# laser_driver.net
KiCad netlist of a schematic drawn in EAGLE
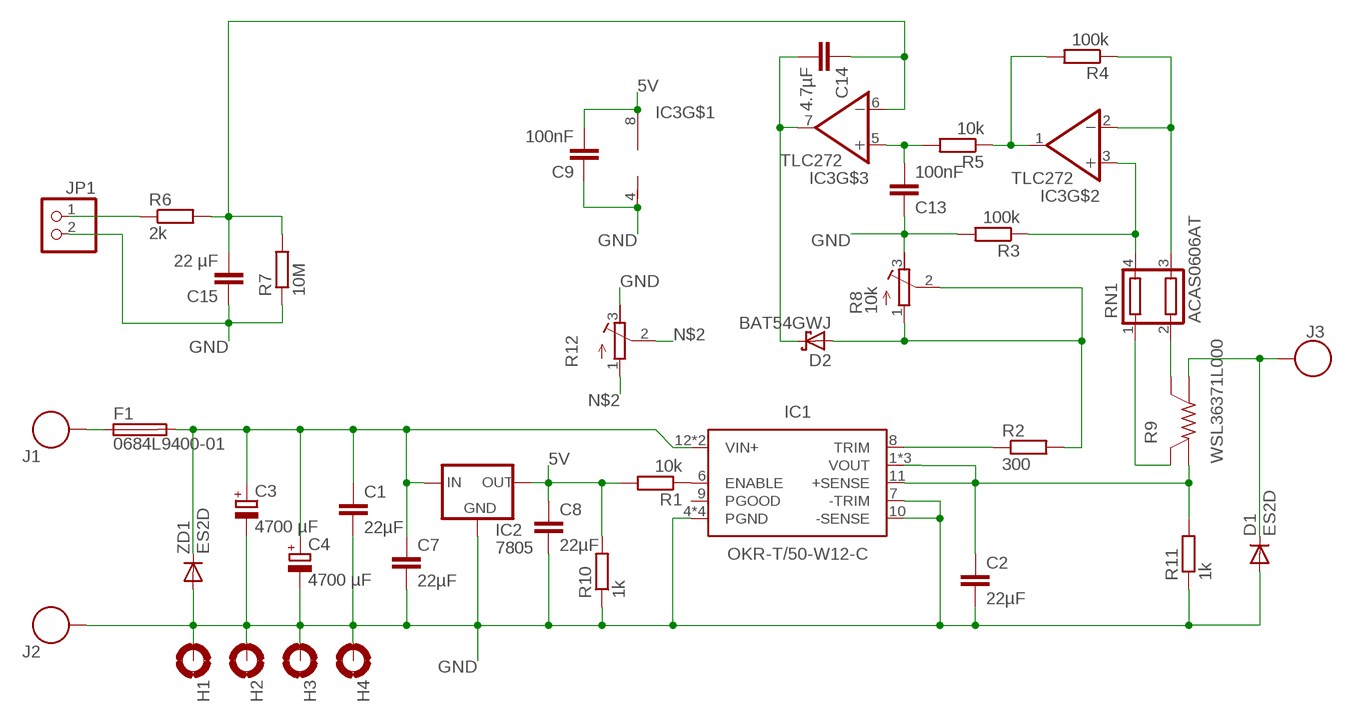
[diagram p0: schematic, sheet 1]

(export (version "E")
  (design (tool "Eeschema 10.0.6"))
  (components
    (comp (ref "C1")
      (value "22µF")
      (footprint "eagle-import:C0805")
      (libsource (lib "eagle-import") (part "C-EUC0805"))
    )
    (comp (ref "C2")
      (value "22µF")
      (footprint "eagle-import:C0805")
      (libsource (lib "eagle-import") (part "C-EUC0805"))
    )
    (comp (ref "C3")
      (value "4700 µF")
      (footprint "eagle-import:E7,5-16")
      (libsource (lib "eagle-import") (part "CPOL-EUE7.5-16"))
    )
    (comp (ref "C4")
      (value "4700 µF")
      (footprint "eagle-import:E7,5-16")
      (libsource (lib "eagle-import") (part "CPOL-EUE7.5-16"))
    )
    (comp (ref "C7")
      (value "22µF")
      (footprint "eagle-import:C0805")
      (libsource (lib "eagle-import") (part "C-EUC0805"))
    )
    (comp (ref "C8")
      (value "22µF")
      (footprint "eagle-import:C0805")
      (libsource (lib "eagle-import") (part "C-EUC0805"))
    )
    (comp (ref "C9")
      (value "100nF")
      (footprint "eagle-import:C0805")
      (libsource (lib "eagle-import") (part "C-EUC0805"))
    )
    (comp (ref "C13")
      (value "100nF")
      (footprint "eagle-import:C0805")
      (libsource (lib "eagle-import") (part "C-EUC0805"))
    )
    (comp (ref "C14")
      (value "4.7µF")
      (footprint "eagle-import:C0805")
      (libsource (lib "eagle-import") (part "C-EUC0805"))
    )
    (comp (ref "C15")
      (value "22 µF")
      (footprint "eagle-import:C0805")
      (libsource (lib "eagle-import") (part "C-EUC0805"))
    )
    (comp (ref "D1")
      (value "ES2D")
      (footprint "eagle-import:SMB")
      (libsource (lib "eagle-import") (part "ES2D"))
    )
    (comp (ref "D2")
      (value "BAT54GWJ")
      (footprint "eagle-import:SOD-123_MINI-SMA")
      (libsource (lib "eagle-import") (part "BAT54GWJ"))
    )
    (comp (ref "F1")
      (value "0684L9400-01")
      (footprint "eagle-import:4818")
      (libsource (lib "eagle-import") (part "0684L9400-01"))
    )
    (comp (ref "H1")
      (value "MOUNT-PAD-ROUND3.0")
      (footprint "eagle-import:3,0-PAD")
      (libsource (lib "eagle-import") (part "MOUNT-PAD-ROUND3.0"))
    )
    (comp (ref "H2")
      (value "MOUNT-PAD-ROUND3.0")
      (footprint "eagle-import:3,0-PAD")
      (libsource (lib "eagle-import") (part "MOUNT-PAD-ROUND3.0"))
    )
    (comp (ref "H3")
      (value "MOUNT-PAD-ROUND3.0")
      (footprint "eagle-import:3,0-PAD")
      (libsource (lib "eagle-import") (part "MOUNT-PAD-ROUND3.0"))
    )
    (comp (ref "H4")
      (value "MOUNT-PAD-ROUND3.0")
      (footprint "eagle-import:3,0-PAD")
      (libsource (lib "eagle-import") (part "MOUNT-PAD-ROUND3.0"))
    )
    (comp (ref "IC1")
      (value "OKR-T/50-W12-C")
      (footprint "eagle-import:OKR-T_50-W12-C")
      (libsource (lib "eagle-import") (part "OKR-T/50-W12-C"))
    )
    (comp (ref "IC2")
      (value "7805")
      (footprint "eagle-import:TO252")
      (libsource (lib "eagle-import") (part "78XX"))
    )
    (comp (ref "IC3")
      (value "TLC272")
      (footprint "eagle-import:SO08")
      (libsource (lib "eagle-import") (part "TLC272"))
    )
    (comp (ref "J1")
      (value "74650073R")
      (footprint "eagle-import:FBGA90-6X15")
      (libsource (lib "eagle-import") (part "74650073R"))
    )
    (comp (ref "J2")
      (value "74650073R")
      (footprint "eagle-import:FBGA90-6X15")
      (libsource (lib "eagle-import") (part "74650073R"))
    )
    (comp (ref "J3")
      (value "74650073R")
      (footprint "eagle-import:FBGA90-6X15")
      (libsource (lib "eagle-import") (part "74650073R"))
    )
    (comp (ref "JP1")
      (value "PINHD-1X2")
      (footprint "eagle-import:1X02")
      (libsource (lib "eagle-import") (part "PINHD-1X2"))
    )
    (comp (ref "R1")
      (value "10k")
      (footprint "eagle-import:R0805")
      (libsource (lib "eagle-import") (part "resistor_348_R-EU_R0805"))
    )
    (comp (ref "R2")
      (value "300")
      (footprint "eagle-import:R0805")
      (libsource (lib "eagle-import") (part "R-EU_R0805"))
    )
    (comp (ref "R3")
      (value "100k")
      (footprint "eagle-import:R0805")
      (libsource (lib "eagle-import") (part "R-EU_R0805"))
    )
    (comp (ref "R4")
      (value "100k")
      (footprint "eagle-import:R0805")
      (libsource (lib "eagle-import") (part "R-EU_R0805"))
    )
    (comp (ref "R5")
      (value "10k")
      (footprint "eagle-import:R0805")
      (libsource (lib "eagle-import") (part "R-EU_R0805"))
    )
    (comp (ref "R6")
      (value "2k")
      (footprint "eagle-import:R0805")
      (libsource (lib "eagle-import") (part "R-EU_R0805"))
    )
    (comp (ref "R7")
      (value "10M")
      (footprint "eagle-import:R0805")
      (libsource (lib "eagle-import") (part "R-EU_R0805"))
    )
    (comp (ref "R8")
      (value "10k")
      (footprint "eagle-import:RTRIM64Y")
      (libsource (lib "eagle-import") (part "R-TRIMM64Y"))
    )
    (comp (ref "R9")
      (value "WSL36371L000")
      (footprint "eagle-import:WSL3637")
      (libsource (lib "eagle-import") (part "WSL3637"))
    )
    (comp (ref "R10")
      (value "1k")
      (footprint "eagle-import:R0805")
      (libsource (lib "eagle-import") (part "R-EU_R0805"))
    )
    (comp (ref "R11")
      (value "1k")
      (footprint "eagle-import:R0805")
      (libsource (lib "eagle-import") (part "R-EU_R0805"))
    )
    (comp (ref "R12")
      (value "R-TRIMM4G/J")
      (footprint "eagle-import:RTRIM4G_J")
      (libsource (lib "eagle-import") (part "R-TRIMM4G/J"))
    )
    (comp (ref "RN1")
      (value "ACAS0606AT")
      (footprint "eagle-import:RESCAXS80P160X150X45-4")
      (libsource (lib "eagle-import") (part "ACAS0606AT"))
    )
    (comp (ref "ZD1")
      (value "ES2D")
      (footprint "eagle-import:SMB")
      (libsource (lib "eagle-import") (part "ES2D"))
    )
  )
  (nets
    (net (code "1") (name "/5V") (class "Default")
      (node (ref "C8") (pin "1") (pinfunction "1_1") (pintype "passive"))
      (node (ref "C9") (pin "2") (pinfunction "2_2") (pintype "passive"))
      (node (ref "IC2") (pin "2") (pinfunction "OUT_2") (pintype "passive"))
      (node (ref "IC3") (pin "8") (pinfunction "V+_8") (pintype "power_in"))
      (node (ref "R1") (pin "2") (pinfunction "2_2") (pintype "passive"))
      (node (ref "R10") (pin "2") (pinfunction "2_2") (pintype "passive"))
    )
    (net (code "2") (name "/GND") (class "Default")
      (node (ref "C1") (pin "2") (pinfunction "2_2") (pintype "passive"))
      (node (ref "C13") (pin "1") (pinfunction "1_1") (pintype "passive"))
      (node (ref "C15") (pin "1") (pinfunction "1_1") (pintype "passive"))
      (node (ref "C2") (pin "2") (pinfunction "2_2") (pintype "passive"))
      (node (ref "C3") (pin "-") (pinfunction "-_-") (pintype "passive"))
      (node (ref "C4") (pin "-") (pinfunction "-_-") (pintype "passive"))
      (node (ref "C7") (pin "2") (pinfunction "2_2") (pintype "passive"))
      (node (ref "C8") (pin "2") (pinfunction "2_2") (pintype "passive"))
      (node (ref "C9") (pin "1") (pinfunction "1_1") (pintype "passive"))
      (node (ref "D1") (pin "A") (pinfunction "A_A") (pintype "passive"))
      (node (ref "H1") (pin "B3,0") (pinfunction "MOUNT_B3,0") (pintype "passive"))
      (node (ref "H2") (pin "B3,0") (pinfunction "MOUNT_B3,0") (pintype "passive"))
      (node (ref "H3") (pin "B3,0") (pinfunction "MOUNT_B3,0") (pintype "passive"))
      (node (ref "H4") (pin "B3,0") (pinfunction "MOUNT_B3,0") (pintype "passive"))
      (node (ref "IC1") (pin "10") (pinfunction "-SENSE_10") (pintype "input"))
      (node (ref "IC1") (pin "14") (pinfunction "PGND_14") (pintype "input"))
      (node (ref "IC1") (pin "15") (pinfunction "PGND_15") (pintype "input"))
      (node (ref "IC1") (pin "4") (pinfunction "PGND_4") (pintype "input"))
      (node (ref "IC1") (pin "5") (pinfunction "PGND_5") (pintype "input"))
      (node (ref "IC1") (pin "7") (pinfunction "-TRIM_7") (pintype "input"))
      (node (ref "IC2") (pin "3") (pinfunction "GND_3") (pintype "input"))
      (node (ref "IC3") (pin "4") (pinfunction "V-_4") (pintype "power_in"))
      (node (ref "J2") (pin "P$1") (pinfunction "1_P$1") (pintype "passive"))
      (node (ref "J2") (pin "P$2") (pinfunction "1_P$2") (pintype "passive"))
      (node (ref "J2") (pin "P$3") (pinfunction "1_P$3") (pintype "passive"))
      (node (ref "J2") (pin "P$4") (pinfunction "1_P$4") (pintype "passive"))
      (node (ref "JP1") (pin "2") (pinfunction "2_2") (pintype "passive"))
      (node (ref "R10") (pin "1") (pinfunction "1_1") (pintype "passive"))
      (node (ref "R11") (pin "1") (pinfunction "1_1") (pintype "passive"))
      (node (ref "R12") (pin "3") (pinfunction "E_3") (pintype "passive"))
      (node (ref "R3") (pin "2") (pinfunction "2_2") (pintype "passive"))
      (node (ref "R7") (pin "1") (pinfunction "1_1") (pintype "passive"))
      (node (ref "R8") (pin "3") (pinfunction "E_3") (pintype "passive"))
      (node (ref "ZD1") (pin "A") (pinfunction "A_A") (pintype "passive"))
    )
    (net (code "3") (name "/N$2") (class "Default")
      (node (ref "D2") (pin "A") (pinfunction "A_A") (pintype "passive"))
      (node (ref "R12") (pin "1") (pinfunction "A_1") (pintype "passive"))
      (node (ref "R12") (pin "2") (pinfunction "S_2") (pintype "passive"))
      (node (ref "R2") (pin "2") (pinfunction "2_2") (pintype "passive"))
      (node (ref "R8") (pin "1") (pinfunction "A_1") (pintype "passive"))
      (node (ref "R8") (pin "2") (pinfunction "S_2") (pintype "passive"))
    )
    (net (code "4") (name "Net-(F1-Pad1)") (class "Default")
      (node (ref "F1") (pin "1") (pinfunction "1_1") (pintype "passive"))
      (node (ref "J1") (pin "P$1") (pinfunction "1_P$1") (pintype "passive"))
      (node (ref "J1") (pin "P$2") (pinfunction "1_P$2") (pintype "passive"))
      (node (ref "J1") (pin "P$3") (pinfunction "1_P$3") (pintype "passive"))
      (node (ref "J1") (pin "P$4") (pinfunction "1_P$4") (pintype "passive"))
    )
    (net (code "5") (name "Net-(IC1-+SENSE)") (class "Default")
      (node (ref "C2") (pin "1") (pinfunction "1_1") (pintype "passive"))
      (node (ref "IC1") (pin "1") (pinfunction "VOUT_1") (pintype "input"))
      (node (ref "IC1") (pin "11") (pinfunction "+SENSE_11") (pintype "input"))
      (node (ref "IC1") (pin "2") (pinfunction "VOUT_2") (pintype "input"))
      (node (ref "IC1") (pin "3") (pinfunction "VOUT_3") (pintype "input"))
      (node (ref "R11") (pin "2") (pinfunction "2_2") (pintype "passive"))
      (node (ref "R9") (pin "I2") (pinfunction "B_I2") (pintype "passive"))
    )
    (net (code "6") (name "Net-(IC1-ENABLE)") (class "Default")
      (node (ref "IC1") (pin "6") (pinfunction "ENABLE_6") (pintype "input"))
      (node (ref "R1") (pin "1") (pinfunction "1_1") (pintype "passive"))
    )
    (net (code "7") (name "Net-(IC1-TRIM)") (class "Default")
      (node (ref "IC1") (pin "8") (pinfunction "TRIM_8") (pintype "input"))
      (node (ref "R2") (pin "1") (pinfunction "1_1") (pintype "passive"))
    )
    (net (code "8") (name "Net-(IC2-IN)") (class "Default")
      (node (ref "C1") (pin "1") (pinfunction "1_1") (pintype "passive"))
      (node (ref "C3") (pin "+") (pinfunction "+_+") (pintype "passive"))
      (node (ref "C4") (pin "+") (pinfunction "+_+") (pintype "passive"))
      (node (ref "C7") (pin "1") (pinfunction "1_1") (pintype "passive"))
      (node (ref "F1") (pin "2") (pinfunction "2_2") (pintype "passive"))
      (node (ref "IC1") (pin "12") (pinfunction "VIN+_12") (pintype "input"))
      (node (ref "IC1") (pin "13") (pinfunction "VIN+_13") (pintype "input"))
      (node (ref "IC2") (pin "1") (pinfunction "IN_1") (pintype "input"))
      (node (ref "ZD1") (pin "C") (pinfunction "C_C") (pintype "passive"))
    )
    (net (code "9") (name "Net-(IC3B-+IN)") (class "Default")
      (node (ref "IC3") (pin "3") (pinfunction "+IN_3") (pintype "input"))
      (node (ref "R3") (pin "1") (pinfunction "1_1") (pintype "passive"))
      (node (ref "RN1") (pin "4") (pinfunction "4_4") (pintype "passive"))
    )
    (net (code "10") (name "Net-(IC3B--IN)") (class "Default")
      (node (ref "IC3") (pin "2") (pinfunction "-IN_2") (pintype "input"))
      (node (ref "R4") (pin "1") (pinfunction "1_1") (pintype "passive"))
      (node (ref "RN1") (pin "3") (pinfunction "3_3") (pintype "passive"))
    )
    (net (code "11") (name "Net-(IC3B-OUT)") (class "Default")
      (node (ref "IC3") (pin "1") (pinfunction "OUT_1") (pintype "output"))
      (node (ref "R4") (pin "2") (pinfunction "2_2") (pintype "passive"))
      (node (ref "R5") (pin "1") (pinfunction "1_1") (pintype "passive"))
    )
    (net (code "12") (name "Net-(IC3C-+IN)") (class "Default")
      (node (ref "C13") (pin "2") (pinfunction "2_2") (pintype "passive"))
      (node (ref "IC3") (pin "5") (pinfunction "+IN_5") (pintype "input"))
      (node (ref "R5") (pin "2") (pinfunction "2_2") (pintype "passive"))
    )
    (net (code "13") (name "Net-(IC3C--IN)") (class "Default")
      (node (ref "C14") (pin "1") (pinfunction "1_1") (pintype "passive"))
      (node (ref "C15") (pin "2") (pinfunction "2_2") (pintype "passive"))
      (node (ref "IC3") (pin "6") (pinfunction "-IN_6") (pintype "input"))
      (node (ref "R6") (pin "2") (pinfunction "2_2") (pintype "passive"))
      (node (ref "R7") (pin "2") (pinfunction "2_2") (pintype "passive"))
    )
    (net (code "14") (name "Net-(IC3C-OUT)") (class "Default")
      (node (ref "C14") (pin "2") (pinfunction "2_2") (pintype "passive"))
      (node (ref "D2") (pin "C") (pinfunction "C_C") (pintype "passive"))
      (node (ref "IC3") (pin "7") (pinfunction "OUT_7") (pintype "output"))
    )
    (net (code "15") (name "Net-(JP1-Pad1)") (class "Default")
      (node (ref "JP1") (pin "1") (pinfunction "1_1") (pintype "passive"))
      (node (ref "R6") (pin "1") (pinfunction "1_1") (pintype "passive"))
    )
    (net (code "16") (name "Net-(R9-A)") (class "Default")
      (node (ref "D1") (pin "C") (pinfunction "C_C") (pintype "passive"))
      (node (ref "J3") (pin "P$1") (pinfunction "1_P$1") (pintype "passive"))
      (node (ref "J3") (pin "P$2") (pinfunction "1_P$2") (pintype "passive"))
      (node (ref "J3") (pin "P$3") (pinfunction "1_P$3") (pintype "passive"))
      (node (ref "J3") (pin "P$4") (pinfunction "1_P$4") (pintype "passive"))
      (node (ref "R9") (pin "I1") (pinfunction "A_I1") (pintype "passive"))
    )
    (net (code "17") (name "Net-(R9-SA)") (class "Default")
      (node (ref "R9") (pin "V1") (pinfunction "SA_V1") (pintype "passive"))
      (node (ref "RN1") (pin "2") (pinfunction "2_2") (pintype "passive"))
    )
    (net (code "18") (name "Net-(R9-SB)") (class "Default")
      (node (ref "R9") (pin "V2") (pinfunction "SB_V2") (pintype "passive"))
      (node (ref "RN1") (pin "1") (pinfunction "1_1") (pintype "passive"))
    )
    (net (code "19") (name "unconnected-(IC1-PGOOD-Pad9)") (class "Default")
      (node (ref "IC1") (pin "9") (pinfunction "PGOOD_9") (pintype "input"))
    )
  )
)
